# CRSC0002.net
KiCad netlist of a schematic drawn in Altium Designer
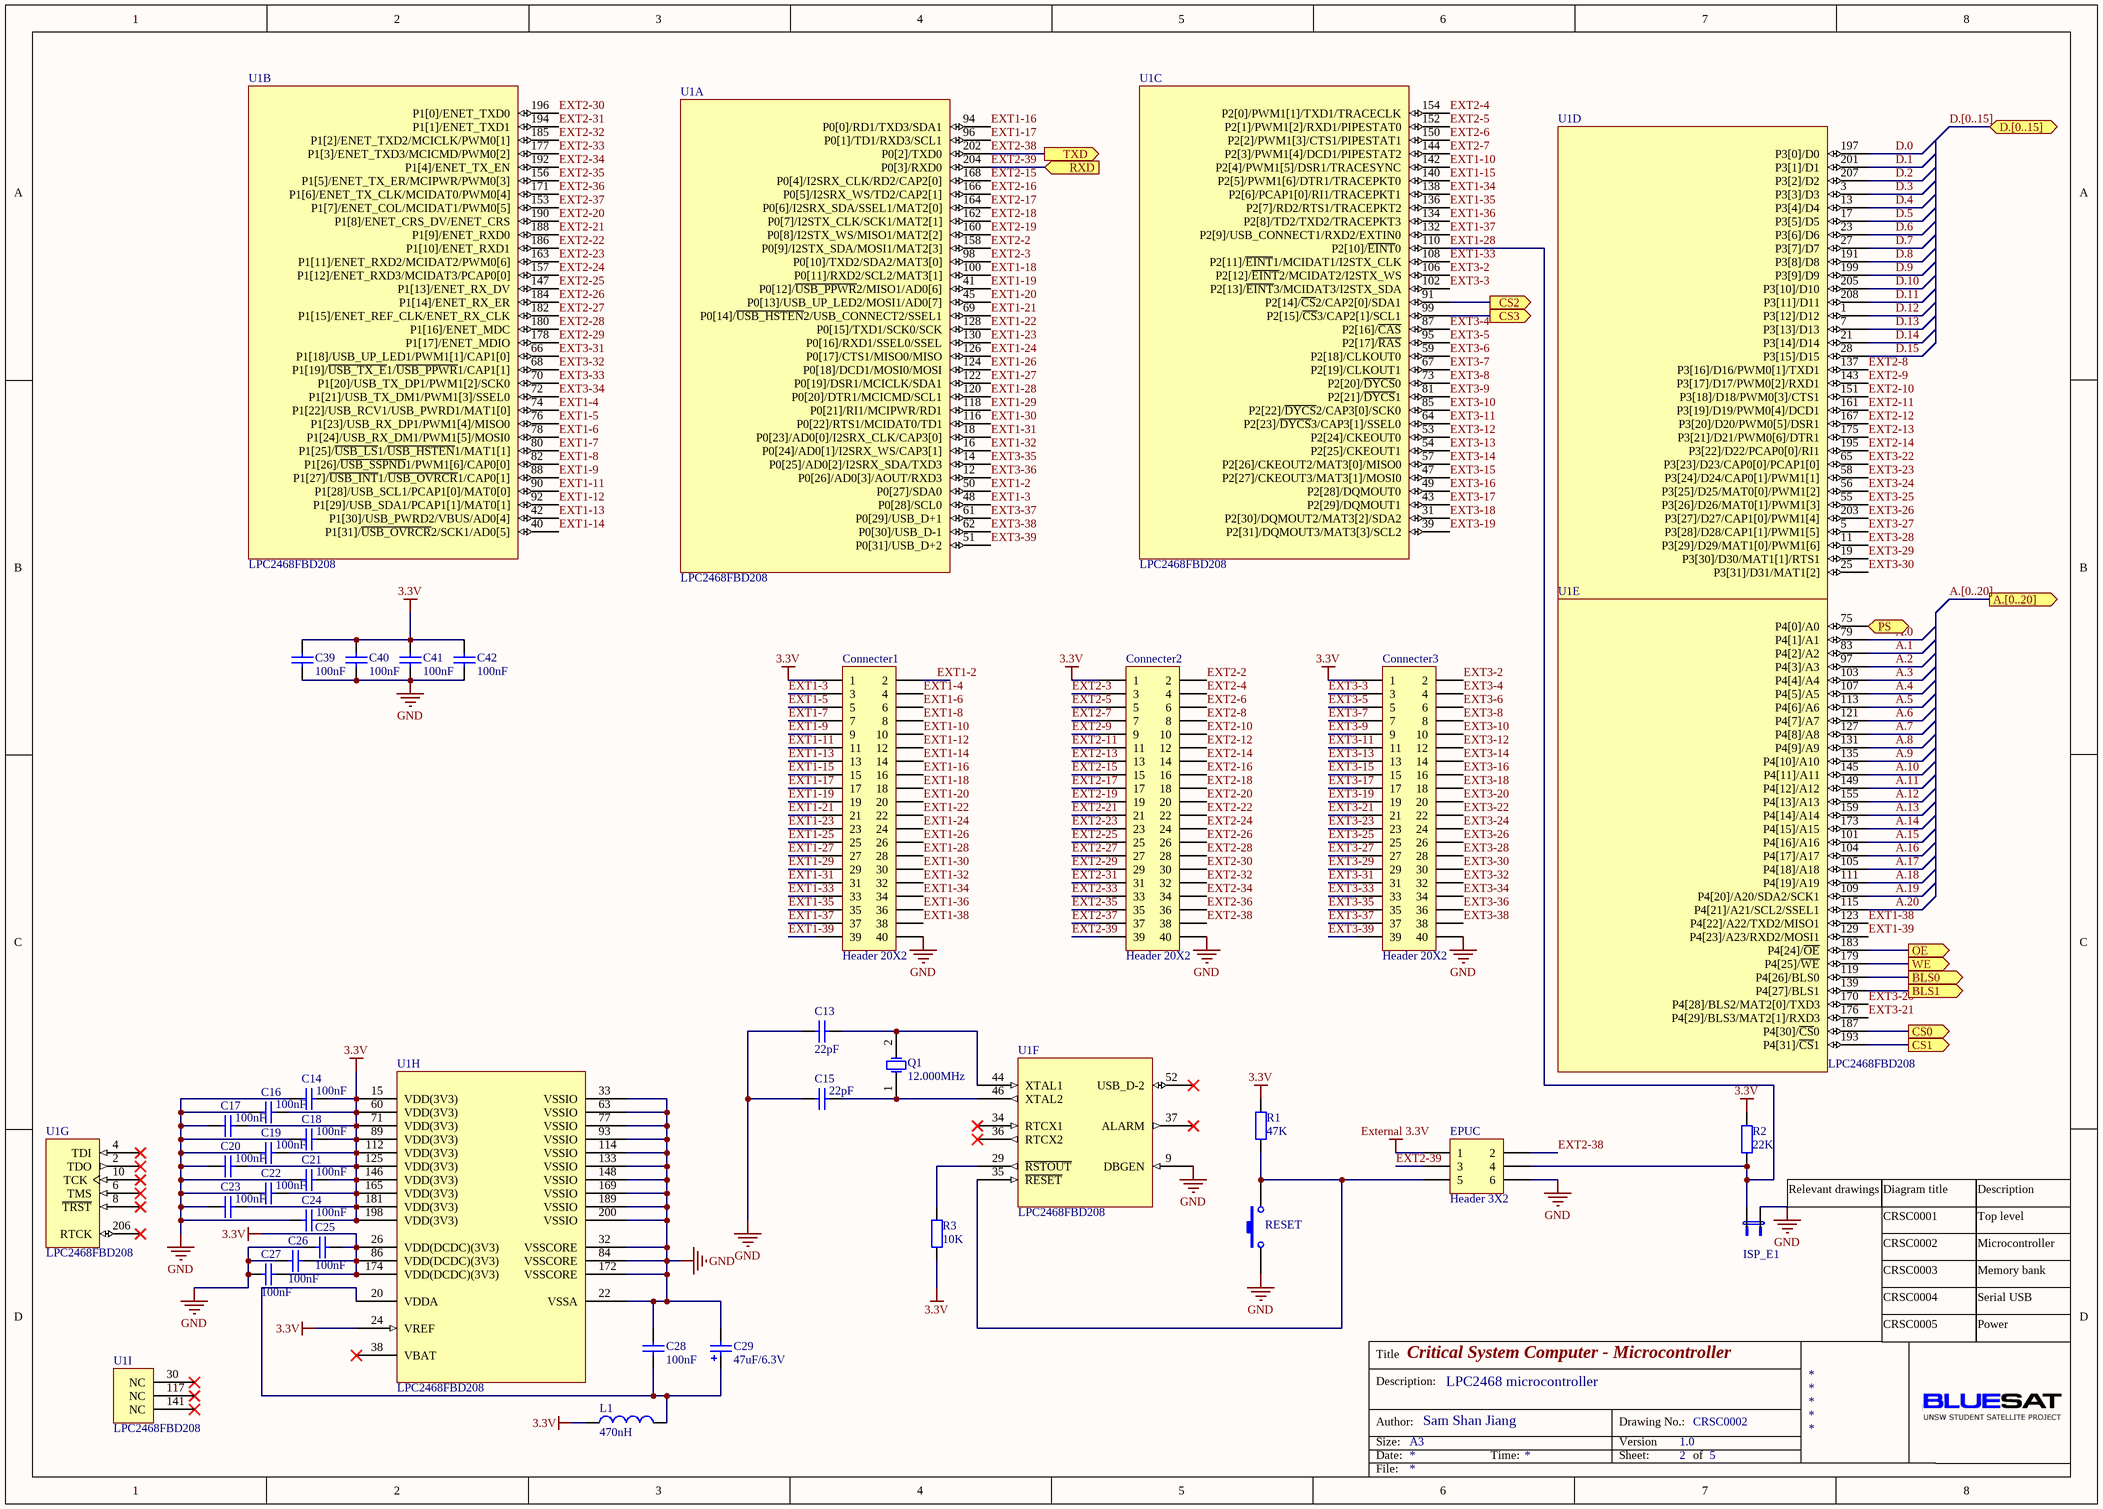
[diagram p0: CRSC0002.SchDoc]

(export (version "E")
  (design (tool "Eeschema 10.0.6"))
  (components
    (comp (ref "C13")
      (value "22pF")
      (footprint "0805")
      (description "Capacitor")
      (fields
        (field (name "MANUFACTURER") "Generic Components")
        (field (name "PUBLISHER") "Altium Hobart Technology Centre")
      )
      (libsource (lib "SELF-MADE_1004") (part "Cap"))
    )
    (comp (ref "C14")
      (value "100nF")
      (footprint "0805")
      (description "Capacitor")
      (fields
        (field (name "MANUFACTURER") "Generic Components")
        (field (name "PUBLISHER") "Altium Hobart Technology Centre")
      )
      (libsource (lib "SELF-MADE_1004") (part "Cap"))
    )
    (comp (ref "C15")
      (value "22pF")
      (footprint "0805")
      (description "Capacitor")
      (fields
        (field (name "MANUFACTURER") "Generic Components")
        (field (name "PUBLISHER") "Altium Hobart Technology Centre")
      )
      (libsource (lib "SELF-MADE_1004") (part "Cap"))
    )
    (comp (ref "C16")
      (value "100nF")
      (footprint "0805")
      (description "Capacitor")
      (fields
        (field (name "MANUFACTURER") "Generic Components")
        (field (name "PUBLISHER") "Altium Hobart Technology Centre")
      )
      (libsource (lib "SELF-MADE_1004") (part "Cap"))
    )
    (comp (ref "C17")
      (value "100nF")
      (footprint "0805")
      (description "Capacitor")
      (fields
        (field (name "MANUFACTURER") "Generic Components")
        (field (name "PUBLISHER") "Altium Hobart Technology Centre")
      )
      (libsource (lib "SELF-MADE_1004") (part "Cap"))
    )
    (comp (ref "C18")
      (value "100nF")
      (footprint "0805")
      (description "Capacitor")
      (fields
        (field (name "MANUFACTURER") "Generic Components")
        (field (name "PUBLISHER") "Altium Hobart Technology Centre")
      )
      (libsource (lib "SELF-MADE_1004") (part "Cap"))
    )
    (comp (ref "C19")
      (value "100nF")
      (footprint "0805")
      (description "Capacitor")
      (fields
        (field (name "MANUFACTURER") "Generic Components")
        (field (name "PUBLISHER") "Altium Hobart Technology Centre")
      )
      (libsource (lib "SELF-MADE_1004") (part "Cap"))
    )
    (comp (ref "C20")
      (value "100nF")
      (footprint "0805")
      (description "Capacitor")
      (fields
        (field (name "MANUFACTURER") "Generic Components")
        (field (name "PUBLISHER") "Altium Hobart Technology Centre")
      )
      (libsource (lib "SELF-MADE_1004") (part "Cap"))
    )
    (comp (ref "C21")
      (value "100nF")
      (footprint "0805")
      (description "Capacitor")
      (fields
        (field (name "MANUFACTURER") "Generic Components")
        (field (name "PUBLISHER") "Altium Hobart Technology Centre")
      )
      (libsource (lib "SELF-MADE_1004") (part "Cap"))
    )
    (comp (ref "C22")
      (value "100nF")
      (footprint "0805")
      (description "Capacitor")
      (fields
        (field (name "MANUFACTURER") "Generic Components")
        (field (name "PUBLISHER") "Altium Hobart Technology Centre")
      )
      (libsource (lib "SELF-MADE_1004") (part "Cap"))
    )
    (comp (ref "C23")
      (value "100nF")
      (footprint "0805")
      (description "Capacitor")
      (fields
        (field (name "MANUFACTURER") "Generic Components")
        (field (name "PUBLISHER") "Altium Hobart Technology Centre")
      )
      (libsource (lib "SELF-MADE_1004") (part "Cap"))
    )
    (comp (ref "C24")
      (value "100nF")
      (footprint "0805")
      (description "Capacitor")
      (fields
        (field (name "MANUFACTURER") "Generic Components")
        (field (name "PUBLISHER") "Altium Hobart Technology Centre")
      )
      (libsource (lib "SELF-MADE_1004") (part "Cap"))
    )
    (comp (ref "C25")
      (value "100nF")
      (footprint "0805")
      (description "Capacitor")
      (fields
        (field (name "MANUFACTURER") "Generic Components")
        (field (name "PUBLISHER") "Altium Hobart Technology Centre")
      )
      (libsource (lib "SELF-MADE_1004") (part "Cap"))
    )
    (comp (ref "C26")
      (value "100nF")
      (footprint "0805")
      (description "Capacitor")
      (fields
        (field (name "MANUFACTURER") "Generic Components")
        (field (name "PUBLISHER") "Altium Hobart Technology Centre")
      )
      (libsource (lib "SELF-MADE_1004") (part "Cap"))
    )
    (comp (ref "C27")
      (value "100nF")
      (footprint "0805")
      (description "Capacitor")
      (fields
        (field (name "MANUFACTURER") "Generic Components")
        (field (name "PUBLISHER") "Altium Hobart Technology Centre")
      )
      (libsource (lib "SELF-MADE_1004") (part "Cap"))
    )
    (comp (ref "C28")
      (value "100nF")
      (footprint "0805")
      (description "Capacitor")
      (fields
        (field (name "MANUFACTURER") "Generic Components")
        (field (name "PUBLISHER") "Altium Hobart Technology Centre")
      )
      (libsource (lib "SELF-MADE_1004") (part "Cap"))
    )
    (comp (ref "C29")
      (value "47uF/6.3V")
      (footprint "1206")
      (description "Polarized Capacitor (Surface Mount)")
      (fields (field (name "PUBLISHER") "Altium Limited"))
      (libsource (lib "SELF-MADE_1004") (part "Cap Pol3"))
    )
    (comp (ref "C39")
      (value "100nF")
      (footprint "0805")
      (description "Capacitor")
      (fields (field (name "Comment") "Cap") (field (name "PUBLISHER") "Altium Limited"))
      (libsource (lib "Miscellaneous Devices") (part "Cap"))
    )
    (comp (ref "C40")
      (value "100nF")
      (footprint "0805")
      (description "Capacitor")
      (fields (field (name "Comment") "Cap") (field (name "PUBLISHER") "Altium Limited"))
      (libsource (lib "Miscellaneous Devices") (part "Cap"))
    )
    (comp (ref "C41")
      (value "100nF")
      (footprint "0805")
      (description "Capacitor")
      (fields (field (name "Comment") "Cap") (field (name "PUBLISHER") "Altium Limited"))
      (libsource (lib "Miscellaneous Devices") (part "Cap"))
    )
    (comp (ref "C42")
      (value "100nF")
      (footprint "0805")
      (description "Capacitor")
      (fields (field (name "Comment") "Cap") (field (name "PUBLISHER") "Altium Limited"))
      (libsource (lib "Miscellaneous Devices") (part "Cap"))
    )
    (comp (ref "Connecter1")
      (value "Header 20X2")
      (footprint "40pins header")
      (description "Header, 20-Pin, Dual row")
      (fields (field (name "MANUFACTURER") "Generic Components"))
      (libsource (lib "SELF-MADE_2905") (part "Header 20X2"))
    )
    (comp (ref "Connecter2")
      (value "Header 20X2")
      (footprint "40pins header")
      (description "Header, 20-Pin, Dual row")
      (fields (field (name "MANUFACTURER") "Generic Components"))
      (libsource (lib "SELF-MADE_1004") (part "Header 20X2"))
    )
    (comp (ref "Connecter3")
      (value "Header 20X2")
      (footprint "40pins header")
      (description "Header, 20-Pin, Dual row")
      (fields (field (name "MANUFACTURER") "Generic Components"))
      (libsource (lib "SELF-MADE_1004") (part "Header 20X2"))
    )
    (comp (ref "EPUC")
      (value "Header 3X2")
      (footprint "6pins header")
      (description "Header, 5-Pin, Dual row")
      (fields (field (name "MANUFACTURER") "Generic Components"))
      (libsource (lib "SELF-MADE_2905") (part "Header 3X2"))
    )
    (comp (ref "ISP_E1")
      (value "2pins jumper")
      (footprint "JUMPER2pins")
      (libsource (lib "SELF-MADE_2905") (part "2pins jumper"))
    )
    (comp (ref "L1")
      (value "470nH")
      (footprint "0805")
      (description "Inductor")
      (fields (field (name "PUBLISHER") "Altium Limited"))
      (libsource (lib "SELF-MADE_1004") (part "Inductor"))
    )
    (comp (ref "Q1")
      (value "12.000MHz")
      (footprint "HC49/4H_SMX")
      (description "Crystal Oscillator")
      (fields (field (name "PUBLISHER") "Altium Limited"))
      (libsource (lib "SELF-MADE_1004") (part "C.O. 2pins"))
    )
    (comp (ref "R1")
      (value "47K")
      (footprint "0805")
      (description "Resistor")
      (fields
        (field (name "MANUFACTURER") "Generic Components")
        (field (name "PUBLISHER") "Altium Hobart Technology Centre")
      )
      (libsource (lib "SELF-MADE_2905") (part "Res2"))
    )
    (comp (ref "R2")
      (value "22K")
      (footprint "0805")
      (description "Resistor")
      (fields
        (field (name "MANUFACTURER") "Generic Components")
        (field (name "PUBLISHER") "Altium Hobart Technology Centre")
      )
      (libsource (lib "SELF-MADE_2905") (part "Res2"))
    )
    (comp (ref "R3")
      (value "10K")
      (footprint "0805")
      (description "Resistor")
      (fields
        (field (name "MANUFACTURER") "Generic Components")
        (field (name "PUBLISHER") "Altium Hobart Technology Centre")
      )
      (libsource (lib "SELF-MADE_1004") (part "Res2"))
    )
    (comp (ref "RESET")
      (value "SW-PB")
      (footprint "E-BIP-P4/D10")
      (description "Switch")
      (fields (field (name "MANUFACTURER") "Generic Components"))
      (libsource (lib "SELF-MADE_2905") (part "SW-PB"))
    )
    (comp (ref "U1")
      (value "LPC2468FBD208")
      (footprint "SOT459-1_M")
      (description "ARM7 16/32-Bit Microcontroller, 512KB Flash, 98KB RAM, 208-Lead LQFP")
      (fields (field (name "PUBLISHER") "Altium Limited"))
      (libsource (lib "SELF-MADE_1004") (part "LPC2468FBD208"))
    )
  )
  (nets
    (net (code "1") (name "/A.0") (class "Default")
      (node (ref "U1") (pin "79") (pinfunction "P4[1]/A1_79") (pintype "bidirectional"))
    )
    (net (code "2") (name "/A.1") (class "Default")
      (node (ref "U1") (pin "83") (pinfunction "P4[2]/A2_83") (pintype "bidirectional"))
    )
    (net (code "3") (name "/A.2") (class "Default")
      (node (ref "U1") (pin "97") (pinfunction "P4[3]/A3_97") (pintype "bidirectional"))
    )
    (net (code "4") (name "/A.3") (class "Default")
      (node (ref "U1") (pin "103") (pinfunction "P4[4]/A4_103") (pintype "bidirectional"))
    )
    (net (code "5") (name "/A.4") (class "Default")
      (node (ref "U1") (pin "107") (pinfunction "P4[5]/A5_107") (pintype "bidirectional"))
    )
    (net (code "6") (name "/A.5") (class "Default")
      (node (ref "U1") (pin "113") (pinfunction "P4[6]/A6_113") (pintype "bidirectional"))
    )
    (net (code "7") (name "/A.6") (class "Default")
      (node (ref "U1") (pin "121") (pinfunction "P4[7]/A7_121") (pintype "bidirectional"))
    )
    (net (code "8") (name "/A.7") (class "Default")
      (node (ref "U1") (pin "127") (pinfunction "P4[8]/A8_127") (pintype "bidirectional"))
    )
    (net (code "9") (name "/A.8") (class "Default")
      (node (ref "U1") (pin "131") (pinfunction "P4[9]/A9_131") (pintype "bidirectional"))
    )
    (net (code "10") (name "/A.9") (class "Default")
      (node (ref "U1") (pin "135") (pinfunction "P4[10]/A10_135") (pintype "bidirectional"))
    )
    (net (code "11") (name "/A.10") (class "Default")
      (node (ref "U1") (pin "145") (pinfunction "P4[11]/A11_145") (pintype "bidirectional"))
    )
    (net (code "12") (name "/A.11") (class "Default")
      (node (ref "U1") (pin "149") (pinfunction "P4[12]/A12_149") (pintype "bidirectional"))
    )
    (net (code "13") (name "/A.12") (class "Default")
      (node (ref "U1") (pin "155") (pinfunction "P4[13]/A13_155") (pintype "bidirectional"))
    )
    (net (code "14") (name "/A.13") (class "Default")
      (node (ref "U1") (pin "159") (pinfunction "P4[14]/A14_159") (pintype "bidirectional"))
    )
    (net (code "15") (name "/A.14") (class "Default")
      (node (ref "U1") (pin "173") (pinfunction "P4[15]/A15_173") (pintype "bidirectional"))
    )
    (net (code "16") (name "/A.15") (class "Default")
      (node (ref "U1") (pin "101") (pinfunction "P4[16]/A16_101") (pintype "bidirectional"))
    )
    (net (code "17") (name "/A.16") (class "Default")
      (node (ref "U1") (pin "104") (pinfunction "P4[17]/A17_104") (pintype "bidirectional"))
    )
    (net (code "18") (name "/A.17") (class "Default")
      (node (ref "U1") (pin "105") (pinfunction "P4[18]/A18_105") (pintype "bidirectional"))
    )
    (net (code "19") (name "/A.18") (class "Default")
      (node (ref "U1") (pin "111") (pinfunction "P4[19]/A19_111") (pintype "bidirectional"))
    )
    (net (code "20") (name "/A.19") (class "Default")
      (node (ref "U1") (pin "109") (pinfunction "P4[20]/A20/SDA2/SCK1_109") (pintype "bidirectional"))
    )
    (net (code "21") (name "/A.20") (class "Default")
      (node (ref "U1") (pin "115") (pinfunction "P4[21]/A21/SCL2/SSEL1_115") (pintype "bidirectional"))
    )
    (net (code "23") (name "/BLS0") (class "Default")
      (node (ref "U1") (pin "119") (pinfunction "P4[26]/BLS0_119") (pintype "bidirectional"))
    )
    (net (code "24") (name "/BLS1") (class "Default")
      (node (ref "U1") (pin "139") (pinfunction "P4[27]/BLS1_139") (pintype "bidirectional"))
    )
    (net (code "25") (name "/CS0") (class "Default")
      (node (ref "U1") (pin "187") (pinfunction "P4[30]/~{CS}0_187") (pintype "bidirectional"))
    )
    (net (code "26") (name "/CS1") (class "Default")
      (node (ref "U1") (pin "193") (pinfunction "P4[31]/~{CS}1_193") (pintype "bidirectional"))
    )
    (net (code "27") (name "/CS2") (class "Default")
      (node (ref "U1") (pin "91") (pinfunction "P2[14]/~{CS}2/CAP2[0]/SDA1_91") (pintype "bidirectional"))
    )
    (net (code "28") (name "/CS3") (class "Default")
      (node (ref "U1") (pin "99") (pinfunction "P2[15]/~{CS}3/CAP2[1]/SCL1_99") (pintype "bidirectional"))
    )
    (net (code "29") (name "/D.0") (class "Default")
      (node (ref "U1") (pin "197") (pinfunction "P3[0]/D0_197") (pintype "bidirectional"))
    )
    (net (code "30") (name "/D.1") (class "Default")
      (node (ref "U1") (pin "201") (pinfunction "P3[1]/D1_201") (pintype "bidirectional"))
    )
    (net (code "31") (name "/D.2") (class "Default")
      (node (ref "U1") (pin "207") (pinfunction "P3[2]/D2_207") (pintype "bidirectional"))
    )
    (net (code "32") (name "/D.3") (class "Default")
      (node (ref "U1") (pin "3") (pinfunction "P3[3]/D3_3") (pintype "bidirectional"))
    )
    (net (code "33") (name "/D.4") (class "Default")
      (node (ref "U1") (pin "13") (pinfunction "P3[4]/D4_13") (pintype "bidirectional"))
    )
    (net (code "34") (name "/D.5") (class "Default")
      (node (ref "U1") (pin "17") (pinfunction "P3[5]/D5_17") (pintype "bidirectional"))
    )
    (net (code "35") (name "/D.6") (class "Default")
      (node (ref "U1") (pin "23") (pinfunction "P3[6]/D6_23") (pintype "bidirectional"))
    )
    (net (code "36") (name "/D.7") (class "Default")
      (node (ref "U1") (pin "27") (pinfunction "P3[7]/D7_27") (pintype "bidirectional"))
    )
    (net (code "37") (name "/D.8") (class "Default")
      (node (ref "U1") (pin "191") (pinfunction "P3[8]/D8_191") (pintype "bidirectional"))
    )
    (net (code "38") (name "/D.9") (class "Default")
      (node (ref "U1") (pin "199") (pinfunction "P3[9]/D9_199") (pintype "bidirectional"))
    )
    (net (code "39") (name "/D.10") (class "Default")
      (node (ref "U1") (pin "205") (pinfunction "P3[10]/D10_205") (pintype "bidirectional"))
    )
    (net (code "40") (name "/D.11") (class "Default")
      (node (ref "U1") (pin "208") (pinfunction "P3[11]/D11_208") (pintype "bidirectional"))
    )
    (net (code "41") (name "/D.12") (class "Default")
      (node (ref "U1") (pin "1") (pinfunction "P3[12]/D12_1") (pintype "bidirectional"))
    )
    (net (code "42") (name "/D.13") (class "Default")
      (node (ref "U1") (pin "7") (pinfunction "P3[13]/D13_7") (pintype "bidirectional"))
    )
    (net (code "43") (name "/D.14") (class "Default")
      (node (ref "U1") (pin "21") (pinfunction "P3[14]/D14_21") (pintype "bidirectional"))
    )
    (net (code "44") (name "/D.15") (class "Default")
      (node (ref "U1") (pin "28") (pinfunction "P3[15]/D15_28") (pintype "bidirectional"))
    )
    (net (code "46") (name "/EXT1-2") (class "Default")
      (node (ref "Connecter1") (pin "2") (pinfunction "2_2") (pintype "passive"))
      (node (ref "U1") (pin "50") (pinfunction "P0[27]/SDA0_50") (pintype "bidirectional"))
    )
    (net (code "47") (name "/EXT1-3") (class "Default")
      (node (ref "Connecter1") (pin "3") (pinfunction "3_3") (pintype "passive"))
      (node (ref "U1") (pin "48") (pinfunction "P0[28]/SCL0_48") (pintype "bidirectional"))
    )
    (net (code "48") (name "/EXT1-4") (class "Default")
      (node (ref "Connecter1") (pin "4") (pinfunction "4_4") (pintype "passive"))
      (node (ref "U1") (pin "74") (pinfunction "P1[22]/USB_RCV1/USB_PWRD1/MAT1[0]_74") (pintype "bidirectional"))
    )
    (net (code "49") (name "/EXT1-5") (class "Default")
      (node (ref "Connecter1") (pin "5") (pinfunction "5_5") (pintype "passive"))
      (node (ref "U1") (pin "76") (pinfunction "P1[23]/USB_RX_DP1/PWM1[4]/MISO0_76") (pintype "bidirectional"))
    )
    (net (code "50") (name "/EXT1-6") (class "Default")
      (node (ref "Connecter1") (pin "6") (pinfunction "6_6") (pintype "passive"))
      (node (ref "U1") (pin "78") (pinfunction "P1[24]/USB_RX_DM1/PWM1[5]/MOSI0_78") (pintype "bidirectional"))
    )
    (net (code "51") (name "/EXT1-7") (class "Default")
      (node (ref "Connecter1") (pin "7") (pinfunction "7_7") (pintype "passive"))
      (node (ref "U1") (pin "80") (pinfunction "P1[25]/~{USB_LS}1/~{USB_HSTEN}1/MAT1[1]_80") (pintype "bidirectional"))
    )
    (net (code "52") (name "/EXT1-8") (class "Default")
      (node (ref "Connecter1") (pin "8") (pinfunction "8_8") (pintype "passive"))
      (node (ref "U1") (pin "82") (pinfunction "P1[26]/~{USB_SSPND}1/PWM1[6]/CAP0[0]_82") (pintype "bidirectional"))
    )
    (net (code "53") (name "/EXT1-9") (class "Default")
      (node (ref "Connecter1") (pin "9") (pinfunction "9_9") (pintype "passive"))
      (node (ref "U1") (pin "88") (pinfunction "P1[27]/~{USB_INT}1/~{USB_OVRCR}1/CAP0[1]_88") (pintype "bidirectional"))
    )
    (net (code "54") (name "/EXT1-10") (class "Default")
      (node (ref "Connecter1") (pin "10") (pinfunction "10_10") (pintype "passive"))
      (node (ref "U1") (pin "142") (pinfunction "P2[4]/PWM1[5]/DSR1/TRACESYNC_142") (pintype "bidirectional"))
    )
    (net (code "55") (name "/EXT1-11") (class "Default")
      (node (ref "Connecter1") (pin "11") (pinfunction "11_11") (pintype "passive"))
      (node (ref "U1") (pin "90") (pinfunction "P1[28]/USB_SCL1/PCAP1[0]/MAT0[0]_90") (pintype "bidirectional"))
    )
    (net (code "56") (name "/EXT1-12") (class "Default")
      (node (ref "Connecter1") (pin "12") (pinfunction "12_12") (pintype "passive"))
      (node (ref "U1") (pin "92") (pinfunction "P1[29]/USB_SDA1/PCAP1[1]/MAT0[1]_92") (pintype "bidirectional"))
    )
    (net (code "57") (name "/EXT1-13") (class "Default")
      (node (ref "Connecter1") (pin "13") (pinfunction "13_13") (pintype "passive"))
      (node (ref "U1") (pin "42") (pinfunction "P1[30]/USB_PWRD2/VBUS/AD0[4]_42") (pintype "bidirectional"))
    )
    (net (code "58") (name "/EXT1-14") (class "Default")
      (node (ref "Connecter1") (pin "14") (pinfunction "14_14") (pintype "passive"))
      (node (ref "U1") (pin "40") (pinfunction "P1[31]/~{USB_OVRCR}2/SCK1/AD0[5]_40") (pintype "bidirectional"))
    )
    (net (code "59") (name "/EXT1-15") (class "Default")
      (node (ref "Connecter1") (pin "15") (pinfunction "15_15") (pintype "passive"))
      (node (ref "U1") (pin "140") (pinfunction "P2[5]/PWM1[6]/DTR1/TRACEPKT0_140") (pintype "bidirectional"))
    )
    (net (code "60") (name "/EXT1-16") (class "Default")
      (node (ref "Connecter1") (pin "16") (pinfunction "16_16") (pintype "passive"))
      (node (ref "U1") (pin "94") (pinfunction "P0[0]/RD1/TXD3/SDA1_94") (pintype "bidirectional"))
    )
    (net (code "61") (name "/EXT1-17") (class "Default")
      (node (ref "Connecter1") (pin "17") (pinfunction "17_17") (pintype "passive"))
      (node (ref "U1") (pin "96") (pinfunction "P0[1]/TD1/RXD3/SCL1_96") (pintype "bidirectional"))
    )
    (net (code "62") (name "/EXT1-18") (class "Default")
      (node (ref "Connecter1") (pin "18") (pinfunction "18_18") (pintype "passive"))
      (node (ref "U1") (pin "100") (pinfunction "P0[11]/RXD2/SCL2/MAT3[1]_100") (pintype "bidirectional"))
    )
    (net (code "63") (name "/EXT1-19") (class "Default")
      (node (ref "Connecter1") (pin "19") (pinfunction "19_19") (pintype "passive"))
      (node (ref "U1") (pin "41") (pinfunction "P0[12]/~{USB_PPWR}2/MISO1/AD0[6]_41") (pintype "bidirectional"))
    )
    (net (code "64") (name "/EXT1-20") (class "Default")
      (node (ref "Connecter1") (pin "20") (pinfunction "20_20") (pintype "passive"))
      (node (ref "U1") (pin "45") (pinfunction "P0[13]/USB_UP_LED2/MOSI1/AD0[7]_45") (pintype "bidirectional"))
    )
    (net (code "65") (name "/EXT1-21") (class "Default")
      (node (ref "Connecter1") (pin "21") (pinfunction "21_21") (pintype "passive"))
      (node (ref "U1") (pin "69") (pinfunction "P0[14]/~{USB_HSTEN}2/USB_CONNECT2/SSEL1_69") (pintype "bidirectional"))
    )
    (net (code "66") (name "/EXT1-22") (class "Default")
      (node (ref "Connecter1") (pin "22") (pinfunction "22_22") (pintype "passive"))
      (node (ref "U1") (pin "128") (pinfunction "P0[15]/TXD1/SCK0/SCK_128") (pintype "bidirectional"))
    )
    (net (code "67") (name "/EXT1-23") (class "Default")
      (node (ref "Connecter1") (pin "23") (pinfunction "23_23") (pintype "passive"))
      (node (ref "U1") (pin "130") (pinfunction "P0[16]/RXD1/SSEL0/SSEL_130") (pintype "bidirectional"))
    )
    (net (code "68") (name "/EXT1-24") (class "Default")
      (node (ref "Connecter1") (pin "24") (pinfunction "24_24") (pintype "passive"))
      (node (ref "U1") (pin "126") (pinfunction "P0[17]/CTS1/MISO0/MISO_126") (pintype "bidirectional"))
    )
    (net (code "69") (name "/EXT1-25") (class "Default")
      (node (ref "Connecter1") (pin "25") (pinfunction "25_25") (pintype "passive"))
    )
    (net (code "70") (name "/EXT1-26") (class "Default")
      (node (ref "Connecter1") (pin "26") (pinfunction "26_26") (pintype "passive"))
      (node (ref "U1") (pin "124") (pinfunction "P0[18]/DCD1/MOSI0/MOSI_124") (pintype "bidirectional"))
    )
    (net (code "71") (name "/EXT1-27") (class "Default")
      (node (ref "Connecter1") (pin "27") (pinfunction "27_27") (pintype "passive"))
      (node (ref "U1") (pin "122") (pinfunction "P0[19]/DSR1/MCICLK/SDA1_122") (pintype "bidirectional"))
    )
    (net (code "72") (name "/EXT1-28") (class "Default")
      (node (ref "Connecter1") (pin "28") (pinfunction "28_28") (pintype "passive"))
      (node (ref "EPUC") (pin "4") (pinfunction "4_4") (pintype "passive"))
      (node (ref "ISP_E1") (pin "1") (pinfunction "1_1") (pintype "passive"))
      (node (ref "R2") (pin "1") (pinfunction "1_1") (pintype "passive"))
      (node (ref "U1") (pin "110") (pinfunction "P2[10]/~{EINT}0_110") (pintype "bidirectional"))
      (node (ref "U1") (pin "120") (pinfunction "P0[20]/DTR1/MCICMD/SCL1_120") (pintype "bidirectional"))
    )
    (net (code "73") (name "/EXT1-29") (class "Default")
      (node (ref "Connecter1") (pin "29") (pinfunction "29_29") (pintype "passive"))
      (node (ref "U1") (pin "118") (pinfunction "P0[21]/RI1/MCIPWR/RD1_118") (pintype "bidirectional"))
    )
    (net (code "74") (name "/EXT1-30") (class "Default")
      (node (ref "Connecter1") (pin "30") (pinfunction "30_30") (pintype "passive"))
      (node (ref "U1") (pin "116") (pinfunction "P0[22]/RTS1/MCIDAT0/TD1_116") (pintype "bidirectional"))
    )
    (net (code "75") (name "/EXT1-31") (class "Default")
      (node (ref "Connecter1") (pin "31") (pinfunction "31_31") (pintype "passive"))
      (node (ref "U1") (pin "18") (pinfunction "P0[23]/AD0[0]/I2SRX_CLK/CAP3[0]_18") (pintype "bidirectional"))
    )
    (net (code "76") (name "/EXT1-32") (class "Default")
      (node (ref "Connecter1") (pin "32") (pinfunction "32_32") (pintype "passive"))
      (node (ref "U1") (pin "16") (pinfunction "P0[24]/AD0[1]/I2SRX_WS/CAP3[1]_16") (pintype "bidirectional"))
    )
    (net (code "77") (name "/EXT1-33") (class "Default")
      (node (ref "Connecter1") (pin "33") (pinfunction "33_33") (pintype "passive"))
      (node (ref "U1") (pin "108") (pinfunction "P2[11]/~{EINT}1/MCIDAT1/I2STX_CLK_108") (pintype "bidirectional"))
    )
    (net (code "78") (name "/EXT1-34") (class "Default")
      (node (ref "Connecter1") (pin "34") (pinfunction "34_34") (pintype "passive"))
      (node (ref "U1") (pin "138") (pinfunction "P2[6]/PCAP1[0]/RI1/TRACEPKT1_138") (pintype "bidirectional"))
    )
    (net (code "79") (name "/EXT1-35") (class "Default")
      (node (ref "Connecter1") (pin "35") (pinfunction "35_35") (pintype "passive"))
      (node (ref "U1") (pin "136") (pinfunction "P2[7]/RD2/RTS1/TRACEPKT2_136") (pintype "bidirectional"))
    )
    (net (code "80") (name "/EXT1-36") (class "Default")
      (node (ref "Connecter1") (pin "36") (pinfunction "36_36") (pintype "passive"))
      (node (ref "U1") (pin "134") (pinfunction "P2[8]/TD2/TXD2/TRACEPKT3_134") (pintype "bidirectional"))
    )
    (net (code "81") (name "/EXT1-37") (class "Default")
      (node (ref "Connecter1") (pin "37") (pinfunction "37_37") (pintype "passive"))
      (node (ref "U1") (pin "132") (pinfunction "P2[9]/USB_CONNECT1/RXD2/EXTIN0_132") (pintype "bidirectional"))
    )
    (net (code "82") (name "/EXT1-38") (class "Default")
      (node (ref "Connecter1") (pin "38") (pinfunction "38_38") (pintype "passive"))
      (node (ref "U1") (pin "123") (pinfunction "P4[22]/A22/TXD2/MISO1_123") (pintype "bidirectional"))
    )
    (net (code "83") (name "/EXT1-39") (class "Default")
      (node (ref "Connecter1") (pin "39") (pinfunction "39_39") (pintype "passive"))
      (node (ref "U1") (pin "129") (pinfunction "P4[23]/A23/RXD2/MOSI1_129") (pintype "bidirectional"))
    )
    (net (code "84") (name "/EXT2-2") (class "Default")
      (node (ref "Connecter2") (pin "2") (pinfunction "2_2") (pintype "passive"))
      (node (ref "U1") (pin "158") (pinfunction "P0[9]/I2STX_SDA/MOSI1/MAT2[3]_158") (pintype "bidirectional"))
    )
    (net (code "85") (name "/EXT2-3") (class "Default")
      (node (ref "Connecter2") (pin "3") (pinfunction "3_3") (pintype "passive"))
      (node (ref "U1") (pin "98") (pinfunction "P0[10]/TXD2/SDA2/MAT3[0]_98") (pintype "bidirectional"))
    )
    (net (code "86") (name "/EXT2-4") (class "Default")
      (node (ref "Connecter2") (pin "4") (pinfunction "4_4") (pintype "passive"))
      (node (ref "U1") (pin "154") (pinfunction "P2[0]/PWM1[1]/TXD1/TRACECLK_154") (pintype "bidirectional"))
    )
    (net (code "87") (name "/EXT2-5") (class "Default")
      (node (ref "Connecter2") (pin "5") (pinfunction "5_5") (pintype "passive"))
      (node (ref "U1") (pin "152") (pinfunction "P2[1]/PWM1[2]/RXD1/PIPESTAT0_152") (pintype "bidirectional"))
    )
    (net (code "88") (name "/EXT2-6") (class "Default")
      (node (ref "Connecter2") (pin "6") (pinfunction "6_6") (pintype "passive"))
      (node (ref "U1") (pin "150") (pinfunction "P2[2]/PWM1[3]/CTS1/PIPESTAT1_150") (pintype "bidirectional"))
    )
    (net (code "89") (name "/EXT2-7") (class "Default")
      (node (ref "Connecter2") (pin "7") (pinfunction "7_7") (pintype "passive"))
      (node (ref "U1") (pin "144") (pinfunction "P2[3]/PWM1[4]/DCD1/PIPESTAT2_144") (pintype "bidirectional"))
    )
    (net (code "90") (name "/EXT2-8") (class "Default")
      (node (ref "Connecter2") (pin "8") (pinfunction "8_8") (pintype "passive"))
      (node (ref "U1") (pin "137") (pinfunction "P3[16]/D16/PWM0[1]/TXD1_137") (pintype "bidirectional"))
    )
    (net (code "91") (name "/EXT2-9") (class "Default")
      (node (ref "Connecter2") (pin "9") (pinfunction "9_9") (pintype "passive"))
      (node (ref "U1") (pin "143") (pinfunction "P3[17]/D17/PWM0[2]/RXD1_143") (pintype "bidirectional"))
    )
    (net (code "92") (name "/EXT2-10") (class "Default")
      (node (ref "Connecter2") (pin "10") (pinfunction "10_10") (pintype "passive"))
      (node (ref "U1") (pin "151") (pinfunction "P3[18]/D18/PWM0[3]/CTS1_151") (pintype "bidirectional"))
    )
    (net (code "93") (name "/EXT2-11") (class "Default")
      (node (ref "Connecter2") (pin "11") (pinfunction "11_11") (pintype "passive"))
      (node (ref "U1") (pin "161") (pinfunction "P3[19]/D19/PWM0[4]/DCD1_161") (pintype "bidirectional"))
    )
    (net (code "94") (name "/EXT2-12") (class "Default")
      (node (ref "Connecter2") (pin "12") (pinfunction "12_12") (pintype "passive"))
      (node (ref "U1") (pin "167") (pinfunction "P3[20]/D20/PWM0[5]/DSR1_167") (pintype "bidirectional"))
    )
    (net (code "95") (name "/EXT2-13") (class "Default")
      (node (ref "Connecter2") (pin "13") (pinfunction "13_13") (pintype "passive"))
      (node (ref "U1") (pin "175") (pinfunction "P3[21]/D21/PWM0[6]/DTR1_175") (pintype "bidirectional"))
    )
    (net (code "96") (name "/EXT2-14") (class "Default")
      (node (ref "Connecter2") (pin "14") (pinfunction "14_14") (pintype "passive"))
      (node (ref "U1") (pin "195") (pinfunction "P3[22]/D22/PCAP0[0]/RI1_195") (pintype "bidirectional"))
    )
    (net (code "97") (name "/EXT2-15") (class "Default")
      (node (ref "Connecter2") (pin "15") (pinfunction "15_15") (pintype "passive"))
      (node (ref "U1") (pin "168") (pinfunction "P0[4]/I2SRX_CLK/RD2/CAP2[0]_168") (pintype "bidirectional"))
    )
    (net (code "98") (name "/EXT2-16") (class "Default")
      (node (ref "Connecter2") (pin "16") (pinfunction "16_16") (pintype "passive"))
      (node (ref "U1") (pin "166") (pinfunction "P0[5]/I2SRX_WS/TD2/CAP2[1]_166") (pintype "bidirectional"))
    )
    (net (code "99") (name "/EXT2-17") (class "Default")
      (node (ref "Connecter2") (pin "17") (pinfunction "17_17") (pintype "passive"))
      (node (ref "U1") (pin "164") (pinfunction "P0[6]/I2SRX_SDA/SSEL1/MAT2[0]_164") (pintype "bidirectional"))
    )
    (net (code "100") (name "/EXT2-18") (class "Default")
      (node (ref "Connecter2") (pin "18") (pinfunction "18_18") (pintype "passive"))
      (node (ref "U1") (pin "162") (pinfunction "P0[7]/I2STX_CLK/SCK1/MAT2[1]_162") (pintype "bidirectional"))
    )
    (net (code "101") (name "/EXT2-19") (class "Default")
      (node (ref "Connecter2") (pin "19") (pinfunction "19_19") (pintype "passive"))
      (node (ref "U1") (pin "160") (pinfunction "P0[8]/I2STX_WS/MISO1/MAT2[2]_160") (pintype "bidirectional"))
    )
    (net (code "102") (name "/EXT2-20") (class "Default")
      (node (ref "Connecter2") (pin "20") (pinfunction "20_20") (pintype "passive"))
      (node (ref "U1") (pin "190") (pinfunction "P1[8]/ENET_CRS_DV/ENET_CRS_190") (pintype "bidirectional"))
    )
    (net (code "103") (name "/EXT2-21") (class "Default")
      (node (ref "Connecter2") (pin "21") (pinfunction "21_21") (pintype "passive"))
      (node (ref "U1") (pin "188") (pinfunction "P1[9]/ENET_RXD0_188") (pintype "bidirectional"))
    )
    (net (code "104") (name "/EXT2-22") (class "Default")
      (node (ref "Connecter2") (pin "22") (pinfunction "22_22") (pintype "passive"))
      (node (ref "U1") (pin "186") (pinfunction "P1[10]/ENET_RXD1_186") (pintype "bidirectional"))
    )
    (net (code "105") (name "/EXT2-23") (class "Default")
      (node (ref "Connecter2") (pin "23") (pinfunction "23_23") (pintype "passive"))
      (node (ref "U1") (pin "163") (pinfunction "P1[11]/ENET_RXD2/MCIDAT2/PWM0[6]_163") (pintype "bidirectional"))
    )
    (net (code "106") (name "/EXT2-24") (class "Default")
      (node (ref "Connecter2") (pin "24") (pinfunction "24_24") (pintype "passive"))
      (node (ref "U1") (pin "157") (pinfunction "P1[12]/ENET_RXD3/MCIDAT3/PCAP0[0]_157") (pintype "bidirectional"))
    )
    (net (code "107") (name "/EXT2-25") (class "Default")
      (node (ref "Connecter2") (pin "25") (pinfunction "25_25") (pintype "passive"))
      (node (ref "U1") (pin "147") (pinfunction "P1[13]/ENET_RX_DV_147") (pintype "bidirectional"))
    )
    (net (code "108") (name "/EXT2-26") (class "Default")
      (node (ref "Connecter2") (pin "26") (pinfunction "26_26") (pintype "passive"))
      (node (ref "U1") (pin "184") (pinfunction "P1[14]/ENET_RX_ER_184") (pintype "bidirectional"))
    )
    (net (code "109") (name "/EXT2-27") (class "Default")
      (node (ref "Connecter2") (pin "27") (pinfunction "27_27") (pintype "passive"))
      (node (ref "U1") (pin "182") (pinfunction "P1[15]/ENET_REF_CLK/ENET_RX_CLK_182") (pintype "bidirectional"))
    )
    (net (code "110") (name "/EXT2-28") (class "Default")
      (node (ref "Connecter2") (pin "28") (pinfunction "28_28") (pintype "passive"))
      (node (ref "U1") (pin "180") (pinfunction "P1[16]/ENET_MDC_180") (pintype "bidirectional"))
    )
    (net (code "111") (name "/EXT2-29") (class "Default")
      (node (ref "Connecter2") (pin "29") (pinfunction "29_29") (pintype "passive"))
      (node (ref "U1") (pin "178") (pinfunction "P1[17]/ENET_MDIO_178") (pintype "bidirectional"))
    )
    (net (code "112") (name "/EXT2-30") (class "Default")
      (node (ref "Connecter2") (pin "30") (pinfunction "30_30") (pintype "passive"))
      (node (ref "U1") (pin "196") (pinfunction "P1[0]/ENET_TXD0_196") (pintype "bidirectional"))
    )
    (net (code "113") (name "/EXT2-31") (class "Default")
      (node (ref "Connecter2") (pin "31") (pinfunction "31_31") (pintype "passive"))
      (node (ref "U1") (pin "194") (pinfunction "P1[1]/ENET_TXD1_194") (pintype "bidirectional"))
    )
    (net (code "114") (name "/EXT2-32") (class "Default")
      (node (ref "Connecter2") (pin "32") (pinfunction "32_32") (pintype "passive"))
      (node (ref "U1") (pin "185") (pinfunction "P1[2]/ENET_TXD2/MCICLK/PWM0[1]_185") (pintype "bidirectional"))
    )
    (net (code "115") (name "/EXT2-33") (class "Default")
      (node (ref "Connecter2") (pin "33") (pinfunction "33_33") (pintype "passive"))
      (node (ref "U1") (pin "177") (pinfunction "P1[3]/ENET_TXD3/MCICMD/PWM0[2]_177") (pintype "bidirectional"))
    )
    (net (code "116") (name "/EXT2-34") (class "Default")
      (node (ref "Connecter2") (pin "34") (pinfunction "34_34") (pintype "passive"))
      (node (ref "U1") (pin "192") (pinfunction "P1[4]/ENET_TX_EN_192") (pintype "bidirectional"))
    )
    (net (code "117") (name "/EXT2-35") (class "Default")
      (node (ref "Connecter2") (pin "35") (pinfunction "35_35") (pintype "passive"))
      (node (ref "U1") (pin "156") (pinfunction "P1[5]/ENET_TX_ER/MCIPWR/PWM0[3]_156") (pintype "bidirectional"))
    )
    (net (code "118") (name "/EXT2-36") (class "Default")
      (node (ref "Connecter2") (pin "36") (pinfunction "36_36") (pintype "passive"))
      (node (ref "U1") (pin "171") (pinfunction "P1[6]/ENET_TX_CLK/MCIDAT0/PWM0[4]_171") (pintype "bidirectional"))
    )
    (net (code "119") (name "/EXT2-37") (class "Default")
      (node (ref "Connecter2") (pin "37") (pinfunction "37_37") (pintype "passive"))
      (node (ref "U1") (pin "153") (pinfunction "P1[7]/ENET_COL/MCIDAT1/PWM0[5]_153") (pintype "bidirectional"))
    )
    (net (code "120") (name "/EXT2-38") (class "Default")
      (node (ref "Connecter2") (pin "38") (pinfunction "38_38") (pintype "passive"))
      (node (ref "EPUC") (pin "2") (pinfunction "2_2") (pintype "passive"))
      (node (ref "U1") (pin "202") (pinfunction "P0[2]/TXD0_202") (pintype "bidirectional"))
    )
    (net (code "121") (name "/EXT2-39") (class "Default")
      (node (ref "Connecter2") (pin "39") (pinfunction "39_39") (pintype "passive"))
      (node (ref "EPUC") (pin "3") (pinfunction "3_3") (pintype "passive"))
      (node (ref "U1") (pin "204") (pinfunction "P0[3]/RXD0_204") (pintype "bidirectional"))
    )
    (net (code "122") (name "/EXT3-2") (class "Default")
      (node (ref "Connecter3") (pin "2") (pinfunction "2_2") (pintype "passive"))
      (node (ref "U1") (pin "106") (pinfunction "P2[12]/~{EINT}2/MCIDAT2/I2STX_WS_106") (pintype "bidirectional"))
    )
    (net (code "123") (name "/EXT3-3") (class "Default")
      (node (ref "Connecter3") (pin "3") (pinfunction "3_3") (pintype "passive"))
      (node (ref "U1") (pin "102") (pinfunction "P2[13]/~{EINT}3/MCIDAT3/I2STX_SDA_102") (pintype "bidirectional"))
    )
    (net (code "124") (name "/EXT3-4") (class "Default")
      (node (ref "Connecter3") (pin "4") (pinfunction "4_4") (pintype "passive"))
      (node (ref "U1") (pin "87") (pinfunction "P2[16]/~{CAS}_87") (pintype "bidirectional"))
    )
    (net (code "125") (name "/EXT3-5") (class "Default")
      (node (ref "Connecter3") (pin "5") (pinfunction "5_5") (pintype "passive"))
      (node (ref "U1") (pin "95") (pinfunction "P2[17]/~{RAS}_95") (pintype "bidirectional"))
    )
    (net (code "126") (name "/EXT3-6") (class "Default")
      (node (ref "Connecter3") (pin "6") (pinfunction "6_6") (pintype "passive"))
      (node (ref "U1") (pin "59") (pinfunction "P2[18]/CLKOUT0_59") (pintype "bidirectional"))
    )
    (net (code "127") (name "/EXT3-7") (class "Default")
      (node (ref "Connecter3") (pin "7") (pinfunction "7_7") (pintype "passive"))
      (node (ref "U1") (pin "67") (pinfunction "P2[19]/CLKOUT1_67") (pintype "bidirectional"))
    )
    (net (code "128") (name "/EXT3-8") (class "Default")
      (node (ref "Connecter3") (pin "8") (pinfunction "8_8") (pintype "passive"))
      (node (ref "U1") (pin "73") (pinfunction "P2[20]/~{DYCS}0_73") (pintype "bidirectional"))
    )
    (net (code "129") (name "/EXT3-9") (class "Default")
      (node (ref "Connecter3") (pin "9") (pinfunction "9_9") (pintype "passive"))
      (node (ref "U1") (pin "81") (pinfunction "P2[21]/~{DYCS}1_81") (pintype "bidirectional"))
    )
    (net (code "130") (name "/EXT3-10") (class "Default")
      (node (ref "Connecter3") (pin "10") (pinfunction "10_10") (pintype "passive"))
      (node (ref "U1") (pin "85") (pinfunction "P2[22]/~{DYCS}2/CAP3[0]/SCK0_85") (pintype "bidirectional"))
    )
    (net (code "131") (name "/EXT3-11") (class "Default")
      (node (ref "Connecter3") (pin "11") (pinfunction "11_11") (pintype "passive"))
      (node (ref "U1") (pin "64") (pinfunction "P2[23]/~{DYCS}3/CAP3[1]/SSEL0_64") (pintype "bidirectional"))
    )
    (net (code "132") (name "/EXT3-12") (class "Default")
      (node (ref "Connecter3") (pin "12") (pinfunction "12_12") (pintype "passive"))
      (node (ref "U1") (pin "53") (pinfunction "P2[24]/CKEOUT0_53") (pintype "bidirectional"))
    )
    (net (code "133") (name "/EXT3-13") (class "Default")
      (node (ref "Connecter3") (pin "13") (pinfunction "13_13") (pintype "passive"))
      (node (ref "U1") (pin "54") (pinfunction "P2[25]/CKEOUT1_54") (pintype "bidirectional"))
    )
    (net (code "134") (name "/EXT3-14") (class "Default")
      (node (ref "Connecter3") (pin "14") (pinfunction "14_14") (pintype "passive"))
      (node (ref "U1") (pin "57") (pinfunction "P2[26]/CKEOUT2/MAT3[0]/MISO0_57") (pintype "bidirectional"))
    )
    (net (code "135") (name "/EXT3-15") (class "Default")
      (node (ref "Connecter3") (pin "15") (pinfunction "15_15") (pintype "passive"))
      (node (ref "U1") (pin "47") (pinfunction "P2[27]/CKEOUT3/MAT3[1]/MOSI0_47") (pintype "bidirectional"))
    )
    (net (code "136") (name "/EXT3-16") (class "Default")
      (node (ref "Connecter3") (pin "16") (pinfunction "16_16") (pintype "passive"))
      (node (ref "U1") (pin "49") (pinfunction "P2[28]/DQMOUT0_49") (pintype "bidirectional"))
    )
    (net (code "137") (name "/EXT3-17") (class "Default")
      (node (ref "Connecter3") (pin "17") (pinfunction "17_17") (pintype "passive"))
      (node (ref "U1") (pin "43") (pinfunction "P2[29]/DQMOUT1_43") (pintype "bidirectional"))
    )
    (net (code "138") (name "/EXT3-18") (class "Default")
      (node (ref "Connecter3") (pin "18") (pinfunction "18_18") (pintype "passive"))
      (node (ref "U1") (pin "31") (pinfunction "P2[30]/DQMOUT2/MAT3[2]/SDA2_31") (pintype "bidirectional"))
    )
    (net (code "139") (name "/EXT3-19") (class "Default")
      (node (ref "Connecter3") (pin "19") (pinfunction "19_19") (pintype "passive"))
      (node (ref "U1") (pin "39") (pinfunction "P2[31]/DQMOUT3/MAT3[3]/SCL2_39") (pintype "bidirectional"))
    )
    (net (code "140") (name "/EXT3-20") (class "Default")
      (node (ref "Connecter3") (pin "20") (pinfunction "20_20") (pintype "passive"))
      (node (ref "U1") (pin "170") (pinfunction "P4[28]/BLS2/MAT2[0]/TXD3_170") (pintype "bidirectional"))
    )
    (net (code "141") (name "/EXT3-21") (class "Default")
      (node (ref "Connecter3") (pin "21") (pinfunction "21_21") (pintype "passive"))
      (node (ref "U1") (pin "176") (pinfunction "P4[29]/BLS3/MAT2[1]/RXD3_176") (pintype "bidirectional"))
    )
    (net (code "142") (name "/EXT3-22") (class "Default")
      (node (ref "Connecter3") (pin "22") (pinfunction "22_22") (pintype "passive"))
      (node (ref "U1") (pin "65") (pinfunction "P3[23]/D23/CAP0[0]/PCAP1[0]_65") (pintype "bidirectional"))
    )
    (net (code "143") (name "/EXT3-23") (class "Default")
      (node (ref "Connecter3") (pin "23") (pinfunction "23_23") (pintype "passive"))
      (node (ref "U1") (pin "58") (pinfunction "P3[24]/D24/CAP0[1]/PWM1[1]_58") (pintype "bidirectional"))
    )
    (net (code "144") (name "/EXT3-24") (class "Default")
      (node (ref "Connecter3") (pin "24") (pinfunction "24_24") (pintype "passive"))
      (node (ref "U1") (pin "56") (pinfunction "P3[25]/D25/MAT0[0]/PWM1[2]_56") (pintype "bidirectional"))
    )
    (net (code "145") (name "/EXT3-25") (class "Default")
      (node (ref "Connecter3") (pin "25") (pinfunction "25_25") (pintype "passive"))
      (node (ref "U1") (pin "55") (pinfunction "P3[26]/D26/MAT0[1]/PWM1[3]_55") (pintype "bidirectional"))
    )
    (net (code "146") (name "/EXT3-26") (class "Default")
      (node (ref "Connecter3") (pin "26") (pinfunction "26_26") (pintype "passive"))
      (node (ref "U1") (pin "203") (pinfunction "P3[27]/D27/CAP1[0]/PWM1[4]_203") (pintype "bidirectional"))
    )
    (net (code "147") (name "/EXT3-27") (class "Default")
      (node (ref "Connecter3") (pin "27") (pinfunction "27_27") (pintype "passive"))
      (node (ref "U1") (pin "5") (pinfunction "P3[28]/D28/CAP1[1]/PWM1[5]_5") (pintype "bidirectional"))
    )
    (net (code "148") (name "/EXT3-28") (class "Default")
      (node (ref "Connecter3") (pin "28") (pinfunction "28_28") (pintype "passive"))
      (node (ref "U1") (pin "11") (pinfunction "P3[29]/D29/MAT1[0]/PWM1[6]_11") (pintype "bidirectional"))
    )
    (net (code "149") (name "/EXT3-29") (class "Default")
      (node (ref "Connecter3") (pin "29") (pinfunction "29_29") (pintype "passive"))
      (node (ref "U1") (pin "19") (pinfunction "P3[30]/D30/MAT1[1]/RTS1_19") (pintype "bidirectional"))
    )
    (net (code "150") (name "/EXT3-30") (class "Default")
      (node (ref "Connecter3") (pin "30") (pinfunction "30_30") (pintype "passive"))
      (node (ref "U1") (pin "25") (pinfunction "P3[31]/D31/MAT1[2]_25") (pintype "bidirectional"))
    )
    (net (code "151") (name "/EXT3-31") (class "Default")
      (node (ref "Connecter3") (pin "31") (pinfunction "31_31") (pintype "passive"))
      (node (ref "U1") (pin "66") (pinfunction "P1[18]/USB_UP_LED1/PWM1[1]/CAP1[0]_66") (pintype "bidirectional"))
    )
    (net (code "152") (name "/EXT3-32") (class "Default")
      (node (ref "Connecter3") (pin "32") (pinfunction "32_32") (pintype "passive"))
      (node (ref "U1") (pin "68") (pinfunction "P1[19]/~{USB_TX_E}1/~{USB_PPWR}1/CAP1[1]_68") (pintype "bidirectional"))
    )
    (net (code "153") (name "/EXT3-33") (class "Default")
      (node (ref "Connecter3") (pin "33") (pinfunction "33_33") (pintype "passive"))
      (node (ref "U1") (pin "70") (pinfunction "P1[20]/USB_TX_DP1/PWM1[2]/SCK0_70") (pintype "bidirectional"))
    )
    (net (code "154") (name "/EXT3-34") (class "Default")
      (node (ref "Connecter3") (pin "34") (pinfunction "34_34") (pintype "passive"))
      (node (ref "U1") (pin "72") (pinfunction "P1[21]/USB_TX_DM1/PWM1[3]/SSEL0_72") (pintype "bidirectional"))
    )
    (net (code "155") (name "/EXT3-35") (class "Default")
      (node (ref "Connecter3") (pin "35") (pinfunction "35_35") (pintype "passive"))
      (node (ref "U1") (pin "14") (pinfunction "P0[25]/AD0[2]/I2SRX_SDA/TXD3_14") (pintype "bidirectional"))
    )
    (net (code "156") (name "/EXT3-36") (class "Default")
      (node (ref "Connecter3") (pin "36") (pinfunction "36_36") (pintype "passive"))
      (node (ref "U1") (pin "12") (pinfunction "P0[26]/AD0[3]/AOUT/RXD3_12") (pintype "bidirectional"))
    )
    (net (code "157") (name "/EXT3-37") (class "Default")
      (node (ref "Connecter3") (pin "37") (pinfunction "37_37") (pintype "passive"))
      (node (ref "U1") (pin "61") (pinfunction "P0[29]/USB_D+1_61") (pintype "bidirectional"))
    )
    (net (code "158") (name "/EXT3-38") (class "Default")
      (node (ref "Connecter3") (pin "38") (pinfunction "38_38") (pintype "passive"))
      (node (ref "U1") (pin "62") (pinfunction "P0[30]/USB_D-1_62") (pintype "bidirectional"))
    )
    (net (code "159") (name "/EXT3-39") (class "Default")
      (node (ref "Connecter3") (pin "39") (pinfunction "39_39") (pintype "passive"))
      (node (ref "U1") (pin "51") (pinfunction "P0[31]/USB_D+2_51") (pintype "bidirectional"))
    )
    (net (code "160") (name "/OE") (class "Default")
      (node (ref "U1") (pin "183") (pinfunction "P4[24]/~{OE}_183") (pintype "bidirectional"))
    )
    (net (code "161") (name "/PS") (class "Default")
      (node (ref "U1") (pin "75") (pinfunction "P4[0]/A0_75") (pintype "bidirectional"))
    )
    (net (code "162") (name "/WE") (class "Default")
      (node (ref "U1") (pin "179") (pinfunction "P4[25]/~{WE}_179") (pintype "bidirectional"))
    )
    (net (code "163") (name "3.3V") (class "Default")
      (node (ref "C14") (pin "2") (pinfunction "2_2") (pintype "passive"))
      (node (ref "C16") (pin "2") (pinfunction "2_2") (pintype "passive"))
      (node (ref "C17") (pin "2") (pinfunction "2_2") (pintype "passive"))
      (node (ref "C18") (pin "2") (pinfunction "2_2") (pintype "passive"))
      (node (ref "C19") (pin "2") (pinfunction "2_2") (pintype "passive"))
      (node (ref "C20") (pin "2") (pinfunction "2_2") (pintype "passive"))
      (node (ref "C21") (pin "2") (pinfunction "2_2") (pintype "passive"))
      (node (ref "C22") (pin "2") (pinfunction "2_2") (pintype "passive"))
      (node (ref "C23") (pin "2") (pinfunction "2_2") (pintype "passive"))
      (node (ref "C24") (pin "2") (pinfunction "2_2") (pintype "passive"))
      (node (ref "C25") (pin "2") (pinfunction "2_2") (pintype "passive"))
      (node (ref "C26") (pin "2") (pinfunction "2_2") (pintype "passive"))
      (node (ref "C27") (pin "2") (pinfunction "2_2") (pintype "passive"))
      (node (ref "C39") (pin "2") (pinfunction "2_2") (pintype "passive"))
      (node (ref "C40") (pin "2") (pinfunction "2_2") (pintype "passive"))
      (node (ref "C41") (pin "2") (pinfunction "2_2") (pintype "passive"))
      (node (ref "C42") (pin "2") (pinfunction "2_2") (pintype "passive"))
      (node (ref "Connecter1") (pin "1") (pinfunction "1_1") (pintype "passive"))
      (node (ref "Connecter2") (pin "1") (pinfunction "1_1") (pintype "passive"))
      (node (ref "Connecter3") (pin "1") (pinfunction "1_1") (pintype "passive"))
      (node (ref "L1") (pin "1") (pinfunction "1_1") (pintype "passive"))
      (node (ref "R1") (pin "2") (pinfunction "2_2") (pintype "passive"))
      (node (ref "R2") (pin "2") (pinfunction "2_2") (pintype "passive"))
      (node (ref "R3") (pin "2") (pinfunction "2_2") (pintype "passive"))
      (node (ref "U1") (pin "112") (pinfunction "VDD(3V3)_112") (pintype "power_in"))
      (node (ref "U1") (pin "125") (pinfunction "VDD(3V3)_125") (pintype "power_in"))
      (node (ref "U1") (pin "146") (pinfunction "VDD(3V3)_146") (pintype "power_in"))
      (node (ref "U1") (pin "15") (pinfunction "VDD(3V3)_15") (pintype "power_in"))
      (node (ref "U1") (pin "165") (pinfunction "VDD(3V3)_165") (pintype "power_in"))
      (node (ref "U1") (pin "174") (pinfunction "VDD(DCDC)(3V3)_174") (pintype "power_in"))
      (node (ref "U1") (pin "181") (pinfunction "VDD(3V3)_181") (pintype "power_in"))
      (node (ref "U1") (pin "198") (pinfunction "VDD(3V3)_198") (pintype "power_in"))
      (node (ref "U1") (pin "24") (pinfunction "VREF_24") (pintype "input"))
      (node (ref "U1") (pin "26") (pinfunction "VDD(DCDC)(3V3)_26") (pintype "power_in"))
      (node (ref "U1") (pin "60") (pinfunction "VDD(3V3)_60") (pintype "power_in"))
      (node (ref "U1") (pin "71") (pinfunction "VDD(3V3)_71") (pintype "power_in"))
      (node (ref "U1") (pin "86") (pinfunction "VDD(DCDC)(3V3)_86") (pintype "power_in"))
      (node (ref "U1") (pin "89") (pinfunction "VDD(3V3)_89") (pintype "power_in"))
    )
    (net (code "164") (name "External 3.3V") (class "Default")
      (node (ref "EPUC") (pin "1") (pinfunction "1_1") (pintype "passive"))
    )
    (net (code "165") (name "GND") (class "Default")
      (node (ref "C13") (pin "2") (pinfunction "2_2") (pintype "passive"))
      (node (ref "C14") (pin "1") (pinfunction "1_1") (pintype "passive"))
      (node (ref "C15") (pin "2") (pinfunction "2_2") (pintype "passive"))
      (node (ref "C16") (pin "1") (pinfunction "1_1") (pintype "passive"))
      (node (ref "C17") (pin "1") (pinfunction "1_1") (pintype "passive"))
      (node (ref "C18") (pin "1") (pinfunction "1_1") (pintype "passive"))
      (node (ref "C19") (pin "1") (pinfunction "1_1") (pintype "passive"))
      (node (ref "C20") (pin "1") (pinfunction "1_1") (pintype "passive"))
      (node (ref "C21") (pin "1") (pinfunction "1_1") (pintype "passive"))
      (node (ref "C22") (pin "1") (pinfunction "1_1") (pintype "passive"))
      (node (ref "C23") (pin "1") (pinfunction "1_1") (pintype "passive"))
      (node (ref "C24") (pin "1") (pinfunction "1_1") (pintype "passive"))
      (node (ref "C25") (pin "1") (pinfunction "1_1") (pintype "passive"))
      (node (ref "C26") (pin "1") (pinfunction "1_1") (pintype "passive"))
      (node (ref "C27") (pin "1") (pinfunction "1_1") (pintype "passive"))
      (node (ref "C28") (pin "2") (pinfunction "2_2") (pintype "passive"))
      (node (ref "C29") (pin "2") (pinfunction "2_2") (pintype "passive"))
      (node (ref "C39") (pin "1") (pinfunction "1_1") (pintype "passive"))
      (node (ref "C40") (pin "1") (pinfunction "1_1") (pintype "passive"))
      (node (ref "C41") (pin "1") (pinfunction "1_1") (pintype "passive"))
      (node (ref "C42") (pin "1") (pinfunction "1_1") (pintype "passive"))
      (node (ref "Connecter1") (pin "40") (pinfunction "40_40") (pintype "passive"))
      (node (ref "Connecter2") (pin "40") (pinfunction "40_40") (pintype "passive"))
      (node (ref "Connecter3") (pin "40") (pinfunction "40_40") (pintype "passive"))
      (node (ref "EPUC") (pin "6") (pinfunction "6_6") (pintype "passive"))
      (node (ref "ISP_E1") (pin "2") (pinfunction "2_2") (pintype "passive"))
      (node (ref "RESET") (pin "1") (pinfunction "1_1") (pintype "passive"))
      (node (ref "U1") (pin "114") (pinfunction "VSSIO_114") (pintype "power_in"))
      (node (ref "U1") (pin "133") (pinfunction "VSSIO_133") (pintype "power_in"))
      (node (ref "U1") (pin "148") (pinfunction "VSSIO_148") (pintype "power_in"))
      (node (ref "U1") (pin "169") (pinfunction "VSSIO_169") (pintype "power_in"))
      (node (ref "U1") (pin "172") (pinfunction "VSSCORE_172") (pintype "power_in"))
      (node (ref "U1") (pin "189") (pinfunction "VSSIO_189") (pintype "power_in"))
      (node (ref "U1") (pin "200") (pinfunction "VSSIO_200") (pintype "power_in"))
      (node (ref "U1") (pin "22") (pinfunction "VSSA_22") (pintype "power_in"))
      (node (ref "U1") (pin "32") (pinfunction "VSSCORE_32") (pintype "power_in"))
      (node (ref "U1") (pin "33") (pinfunction "VSSIO_33") (pintype "power_in"))
      (node (ref "U1") (pin "63") (pinfunction "VSSIO_63") (pintype "power_in"))
      (node (ref "U1") (pin "77") (pinfunction "VSSIO_77") (pintype "power_in"))
      (node (ref "U1") (pin "84") (pinfunction "VSSCORE_84") (pintype "power_in"))
      (node (ref "U1") (pin "9") (pinfunction "DBGEN_9") (pintype "input"))
      (node (ref "U1") (pin "93") (pinfunction "VSSIO_93") (pintype "power_in"))
    )
    (net (code "166") (name "Net-(Q1-OSC1)") (class "Default")
      (node (ref "C15") (pin "1") (pinfunction "1_1") (pintype "passive"))
      (node (ref "Q1") (pin "1") (pinfunction "OSC1_1") (pintype "passive"))
      (node (ref "U1") (pin "46") (pinfunction "XTAL2_46") (pintype "output"))
    )
    (net (code "167") (name "Net-(Q1-OSC2)") (class "Default")
      (node (ref "C13") (pin "1") (pinfunction "1_1") (pintype "passive"))
      (node (ref "Q1") (pin "2") (pinfunction "OSC2_2") (pintype "passive"))
      (node (ref "U1") (pin "44") (pinfunction "XTAL1_44") (pintype "input"))
    )
    (net (code "168") (name "Net-(U1F-~{RESET})") (class "Default")
      (node (ref "EPUC") (pin "5") (pinfunction "5_5") (pintype "passive"))
      (node (ref "R1") (pin "1") (pinfunction "1_1") (pintype "passive"))
      (node (ref "RESET") (pin "2") (pinfunction "2_2") (pintype "passive"))
      (node (ref "U1") (pin "35") (pinfunction "~{RESET}_35") (pintype "input"))
    )
    (net (code "169") (name "Net-(U1F-~{RSTOUT})") (class "Default")
      (node (ref "R3") (pin "1") (pinfunction "1_1") (pintype "passive"))
      (node (ref "U1") (pin "29") (pinfunction "~{RSTOUT}_29") (pintype "output"))
    )
    (net (code "170") (name "Net-(U1H-VDDA)") (class "Default")
      (node (ref "C28") (pin "1") (pinfunction "1_1") (pintype "passive"))
      (node (ref "C29") (pin "1") (pinfunction "1_1") (pintype "passive"))
      (node (ref "L1") (pin "2") (pinfunction "2_2") (pintype "passive"))
      (node (ref "U1") (pin "20") (pinfunction "VDDA_20") (pintype "power_in"))
    )
    (net (code "171") (name "unconnected-(U1F-ALARM-Pad37)") (class "Default")
      (node (ref "U1") (pin "37") (pinfunction "ALARM_37") (pintype "output+no_connect"))
    )
    (net (code "172") (name "unconnected-(U1F-RTCX1-Pad34)") (class "Default")
      (node (ref "U1") (pin "34") (pinfunction "RTCX1_34") (pintype "input+no_connect"))
    )
    (net (code "173") (name "unconnected-(U1F-RTCX2-Pad36)") (class "Default")
      (node (ref "U1") (pin "36") (pinfunction "RTCX2_36") (pintype "output+no_connect"))
    )
    (net (code "174") (name "unconnected-(U1F-USB_D-2-Pad52)") (class "Default")
      (node (ref "U1") (pin "52") (pinfunction "USB_D-2_52") (pintype "bidirectional+no_connect"))
    )
    (net (code "175") (name "unconnected-(U1G-RTCK-Pad206)") (class "Default")
      (node (ref "U1") (pin "206") (pinfunction "RTCK_206") (pintype "bidirectional+no_connect"))
    )
    (net (code "176") (name "unconnected-(U1G-TCK-Pad10)") (class "Default")
      (node (ref "U1") (pin "10") (pinfunction "TCK_10") (pintype "input+no_connect"))
    )
    (net (code "177") (name "unconnected-(U1G-TDI-Pad4)") (class "Default")
      (node (ref "U1") (pin "4") (pinfunction "TDI_4") (pintype "input+no_connect"))
    )
    (net (code "178") (name "unconnected-(U1G-TDO-Pad2)") (class "Default")
      (node (ref "U1") (pin "2") (pinfunction "TDO_2") (pintype "output+no_connect"))
    )
    (net (code "179") (name "unconnected-(U1G-TMS-Pad6)") (class "Default")
      (node (ref "U1") (pin "6") (pinfunction "TMS_6") (pintype "input+no_connect"))
    )
    (net (code "180") (name "unconnected-(U1G-~{TRST}-Pad8)") (class "Default")
      (node (ref "U1") (pin "8") (pinfunction "~{TRST}_8") (pintype "input+no_connect"))
    )
    (net (code "181") (name "unconnected-(U1H-VBAT-Pad38)") (class "Default")
      (node (ref "U1") (pin "38") (pinfunction "VBAT_38") (pintype "power_in+no_connect"))
    )
    (net (code "182") (name "unconnected-(U1I-NC-Pad30)") (class "Default")
      (node (ref "U1") (pin "30") (pinfunction "NC_30") (pintype "passive+no_connect"))
    )
    (net (code "183") (name "unconnected-(U1I-NC-Pad117)") (class "Default")
      (node (ref "U1") (pin "117") (pinfunction "NC_117") (pintype "passive+no_connect"))
    )
    (net (code "184") (name "unconnected-(U1I-NC-Pad141)") (class "Default")
      (node (ref "U1") (pin "141") (pinfunction "NC_141") (pintype "passive+no_connect"))
    )
  )
)
